# 02-MCU.net
KiCad netlist of a schematic drawn in Altium Designer
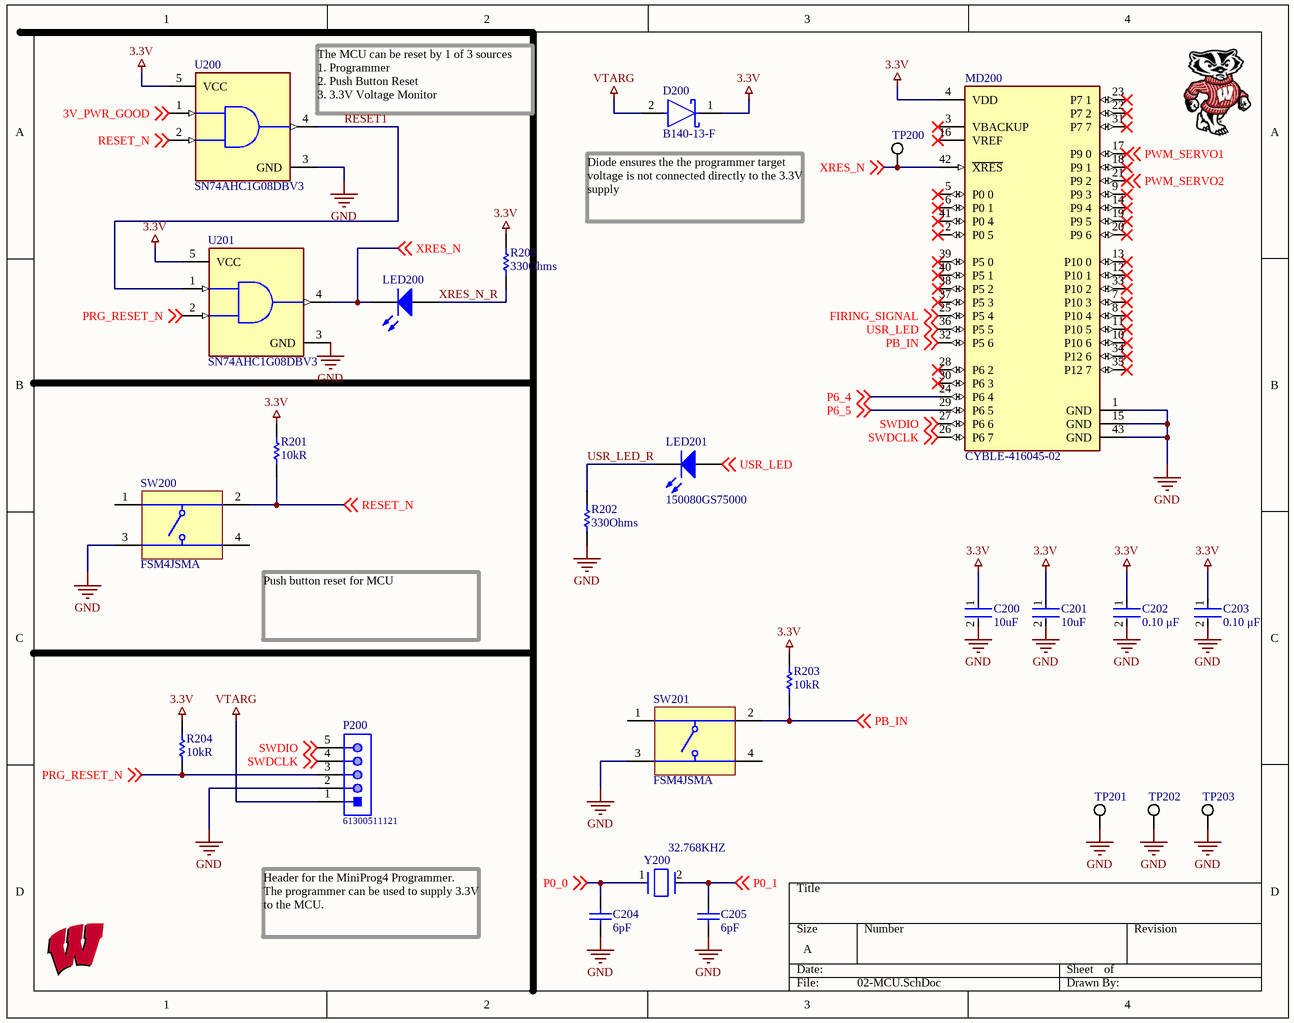
[diagram p0: 02-MCU.SchDoc]

(export (version "E")
  (design (tool "Eeschema 10.0.6"))
  (components
    (comp (ref "C200")
      (value "10uF")
      (footprint "FP-C0805C-DG-MFG")
      (description "CAP CER 10UF 10V X5R 0805")
      (fields (field (name "TOLERANCE") "10%") (field (name "MANUFACTURER PART NUMBER") "C0805C106K8PACTU"))
      (libsource (lib "Altium Content Vault") (part "11868f565c42a9108669ba33697ecf6"))
    )
    (comp (ref "C201")
      (value "10uF")
      (footprint "FP-C0805C-DG-MFG")
      (description "CAP CER 10UF 10V X5R 0805")
      (fields (field (name "TOLERANCE") "10%") (field (name "MANUFACTURER PART NUMBER") "C0805C106K8PACTU"))
      (libsource (lib "Altium Content Vault") (part "11868f565c42a9108669ba33697ecf6"))
    )
    (comp (ref "C202")
      (value "0.10 μF")
      (footprint "FP-C0805C-DN-MFG")
      (description "CAP CER 0.1UF 50V X7R 0805")
      (fields
        (field (name "MANUFACTURER PART NUMBER") "C0805C104K5RACTU")
        (field (name "MANUFACTURER") "KEMET")
      )
      (libsource (lib "Altium Content Vault") (part "b4654b650e69147ec39a6b967a45e02"))
    )
    (comp (ref "C203")
      (value "0.10 μF")
      (footprint "FP-C0805C-DN-MFG")
      (description "CAP CER 0.1UF 50V X7R 0805")
      (fields
        (field (name "MANUFACTURER PART NUMBER") "C0805C104K5RACTU")
        (field (name "MANUFACTURER") "KEMET")
      )
      (libsource (lib "Altium Content Vault") (part "b4654b650e69147ec39a6b967a45e02"))
    )
    (comp (ref "C204")
      (value "08055A6R0CAT2A")
      (footprint "CAPC2013X94X50LL20T25")
      (fields (field (name "MANUFACTURER") "AVX Interconnect / Elco") (field (name "CAPACITANCE") "6pF"))
      (libsource (lib "Altium Content Vault") (part "CAP"))
    )
    (comp (ref "C205")
      (value "08055A6R0CAT2A")
      (footprint "CAPC2013X94X50LL20T25")
      (fields (field (name "MANUFACTURER") "AVX Interconnect / Elco") (field (name "CAPACITANCE") "6pF"))
      (libsource (lib "Altium Content Vault") (part "CAP"))
    )
    (comp (ref "D200")
      (value "B140-13-F")
      (footprint "FP-SMA-MFG")
      (description "DIODE SCHOTTKY 40V 1A SMA")
      (libsource (lib "Altium Content Vault") (part "1d6ec82d83fb6aee721767c19dac4b9"))
    )
    (comp (ref "LED200")
      (value "150080RS75000")
      (footprint "0805_A")
      (description "SMD mono-color Chip LED, WL-SMCW, Red")
      (fields (field (name "MANUFACTURER") "Wuerth Elektronik"))
      (libsource (lib "Altium Content Vault") (part "WE-LED_K1A2-2"))
    )
    (comp (ref "LED201")
      (value "150080GS75000")
      (footprint "0805_A")
      (description "SMD mono-color Chip LED, WL-SMCW, Green")
      (fields (field (name "MANUFACTURER") "Wuerth Elektronik"))
      (libsource (lib "Altium Content Vault") (part "WE-LED_K1A2-2"))
    )
    (comp (ref "MD200")
      (value "CYBLE-416045-02")
      (footprint "FP-CYBLE-416045-02-MFG")
      (description "RF TXRX MOD BLUETOOTH TRACE ANT")
      (fields
        (field (name "OCTOPART") "https://octopart.com/cyble-416045-02-cypress+semiconductor-96386825")
        (field (name "MANUFACTURER") "Cypress Semiconductor")
      )
      (libsource (lib "Altium Content Vault") (part "10a29a4e77099fbb6f911efb04878b1"))
    )
    (comp (ref "P200")
      (value "61300511121")
      (footprint "61300511121")
      (description "THT Vertical Pin Header WR-PHD, Pitch 2.54 mm, Single Row, 5 pins")
      (fields (field (name "MANUFACTURER") "Wurth Elektronik") (field (name "PUBLISHER") "WurthElektronik"))
      (libsource (lib "Altium Content Vault") (part "WE-CN-1P-M-R5"))
    )
    (comp (ref "R200")
      (value "RC0805FR-07330RL")
      (footprint "RESC2013X60X35LL10T20")
      (description "Chip Resistor, 330 Ohm, +/- 1%, 125 mW, -55 to 155 degC, 0805 (2012 Metric), RoHS, Tape and Reel")
      (fields
        (field (name "MANUFACTURER") "Yageo")
        (field (name "TOLERANCE") "1%")
        (field (name "RESISTANCE") "330Ohms")
      )
      (libsource (lib "Altium Content Vault") (part "RES-2"))
    )
    (comp (ref "R201")
      (value "RC0805FR-0710KL")
      (footprint "RESC2013X60X35NL10T20")
      (description "Chip Resistor, 10 KOhm, +/- 1%, 0.125 W, -55 to 155 degC, 0805 (2012 Metric), RoHS, Tape and Reel")
      (fields
        (field (name "MANUFACTURER") "Yageo")
        (field (name "RESISTANCE") "10kR")
        (field (name "TOLERANCE") "1%")
      )
      (libsource (lib "Altium Content Vault") (part "RES-2"))
    )
    (comp (ref "R202")
      (value "RC0805FR-07330RL")
      (footprint "RESC2013X60X35LL10T20")
      (description "Chip Resistor, 330 Ohm, +/- 1%, 125 mW, -55 to 155 degC, 0805 (2012 Metric), RoHS, Tape and Reel")
      (fields
        (field (name "MANUFACTURER") "Yageo")
        (field (name "TOLERANCE") "1%")
        (field (name "RESISTANCE") "330Ohms")
      )
      (libsource (lib "Altium Content Vault") (part "RES-2"))
    )
    (comp (ref "R203")
      (value "RC0805FR-0710KL")
      (footprint "RESC2013X60X35NL10T20")
      (description "Chip Resistor, 10 KOhm, +/- 1%, 0.125 W, -55 to 155 degC, 0805 (2012 Metric), RoHS, Tape and Reel")
      (fields
        (field (name "MANUFACTURER") "Yageo")
        (field (name "RESISTANCE") "10kR")
        (field (name "TOLERANCE") "1%")
      )
      (libsource (lib "Altium Content Vault") (part "RES-2"))
    )
    (comp (ref "R204")
      (value "RC0805FR-0710KL")
      (footprint "RESC2013X60X35NL10T20")
      (description "Chip Resistor, 10 KOhm, +/- 1%, 0.125 W, -55 to 155 degC, 0805 (2012 Metric), RoHS, Tape and Reel")
      (fields
        (field (name "MANUFACTURER") "Yageo")
        (field (name "RESISTANCE") "10kR")
        (field (name "TOLERANCE") "1%")
      )
      (libsource (lib "Altium Content Vault") (part "RES-2"))
    )
    (comp (ref "SW200")
      (value "FSM4JSMA")
      (footprint "TECO-FSM4JSMA_V")
      (description "Swicth, SPST, 24 V, -35 to 85 degC, 4-Pin SMD, RoHS, Tape and Reel")
      (fields (field (name "MANUFACTURER") "TE Connectivity"))
      (libsource (lib "Altium Content Vault") (part "SW-SPST-4_A"))
    )
    (comp (ref "SW201")
      (value "FSM4JSMA")
      (footprint "TECO-FSM4JSMA_V")
      (description "Swicth, SPST, 24 V, -35 to 85 degC, 4-Pin SMD, RoHS, Tape and Reel")
      (fields (field (name "MANUFACTURER") "TE Connectivity"))
      (libsource (lib "Altium Content Vault") (part "SW-SPST-4_A"))
    )
    (comp (ref "TP200")
      (value "5019")
      (footprint "KSTN-5019_V")
      (description "Test Point, 1 Position SMD, RoHS, Tape and Reel")
      (libsource (lib "Altium Content Vault") (part "TESTPOINT_WHITE"))
    )
    (comp (ref "TP201")
      (value "5019")
      (footprint "KSTN-5019_V")
      (description "Test Point, 1 Position SMD, RoHS, Tape and Reel")
      (libsource (lib "Altium Content Vault") (part "TESTPOINT_WHITE"))
    )
    (comp (ref "TP202")
      (value "5019")
      (footprint "KSTN-5019_V")
      (description "Test Point, 1 Position SMD, RoHS, Tape and Reel")
      (libsource (lib "Altium Content Vault") (part "TESTPOINT_WHITE"))
    )
    (comp (ref "TP203")
      (value "5019")
      (footprint "KSTN-5019_V")
      (description "Test Point, 1 Position SMD, RoHS, Tape and Reel")
      (libsource (lib "Altium Content Vault") (part "TESTPOINT_WHITE"))
    )
    (comp (ref "U200")
      (value "SN74AHC1G08DBV3")
      (footprint "FP-DBV0005A-IPC_C")
      (description "IC GATE AND 1CH 2-INP SOT23-5")
      (libsource (lib "Altium Content Vault") (part "675e79b427d6219a5295bf943425e1c"))
    )
    (comp (ref "U201")
      (value "SN74AHC1G08DBV3")
      (footprint "FP-DBV0005A-IPC_C")
      (description "IC GATE AND 1CH 2-INP SOT23-5")
      (libsource (lib "Altium Content Vault") (part "675e79b427d6219a5295bf943425e1c"))
    )
    (comp (ref "Y200")
      (value "32.768KHZ")
      (footprint "FP-ABS07-120-MFG")
      (description "CRYSTAL 32.7680KHZ 6PF SMD")
      (fields (field (name "TOLERANCE") "20ppm"))
      (libsource (lib "Altium Content Vault") (part "c23a69dc6c9e2f18f2079038eb95dd1"))
    )
  )
  (nets
    (net (code "1") (name "/RESET1") (class "Default")
      (node (ref "U200") (pin "4") (pinfunction "Y_4") (pintype "output"))
      (node (ref "U201") (pin "1") (pinfunction "A_1") (pintype "input"))
    )
    (net (code "2") (name "/USR_LED_R") (class "Default")
      (node (ref "LED201") (pin "1") (pinfunction "K_1") (pintype "passive"))
      (node (ref "R202") (pin "2") (pinfunction "2_2") (pintype "passive"))
    )
    (net (code "3") (name "/XRES_N_R") (class "Default")
      (node (ref "LED200") (pin "2") (pinfunction "A_2") (pintype "passive"))
      (node (ref "R200") (pin "1") (pinfunction "1_1") (pintype "passive"))
    )
    (net (code "4") (name "3.3V") (class "Default")
      (node (ref "C200") (pin "1") (pinfunction "1_1") (pintype "passive"))
      (node (ref "C201") (pin "1") (pinfunction "1_1") (pintype "passive"))
      (node (ref "C202") (pin "1") (pinfunction "1_1") (pintype "passive"))
      (node (ref "C203") (pin "1") (pinfunction "1_1") (pintype "passive"))
      (node (ref "D200") (pin "1") (pinfunction "C_1") (pintype "passive"))
      (node (ref "MD200") (pin "4") (pinfunction "VDD_4") (pintype "power_in"))
      (node (ref "R200") (pin "2") (pinfunction "2_2") (pintype "passive"))
      (node (ref "R201") (pin "2") (pinfunction "2_2") (pintype "passive"))
      (node (ref "R203") (pin "2") (pinfunction "2_2") (pintype "passive"))
      (node (ref "R204") (pin "2") (pinfunction "2_2") (pintype "passive"))
      (node (ref "U200") (pin "5") (pinfunction "VCC_5") (pintype "power_in"))
      (node (ref "U201") (pin "5") (pinfunction "VCC_5") (pintype "power_in"))
    )
    (net (code "5") (name "3V_PWR_GOOD") (class "Default")
      (node (ref "U200") (pin "1") (pinfunction "A_1") (pintype "input"))
    )
    (net (code "6") (name "FIRING_SIGNAL") (class "Default")
      (node (ref "MD200") (pin "25") (pinfunction "P5_4_25") (pintype "bidirectional"))
    )
    (net (code "7") (name "GND") (class "Default")
      (node (ref "C200") (pin "2") (pinfunction "2_2") (pintype "passive"))
      (node (ref "C201") (pin "2") (pinfunction "2_2") (pintype "passive"))
      (node (ref "C202") (pin "2") (pinfunction "2_2") (pintype "passive"))
      (node (ref "C203") (pin "2") (pinfunction "2_2") (pintype "passive"))
      (node (ref "C204") (pin "1") (pinfunction "1_1") (pintype "passive"))
      (node (ref "C205") (pin "1") (pinfunction "1_1") (pintype "passive"))
      (node (ref "MD200") (pin "1") (pinfunction "GND_1") (pintype "power_in"))
      (node (ref "MD200") (pin "15") (pinfunction "GND_15") (pintype "power_in"))
      (node (ref "MD200") (pin "43") (pinfunction "GND_43") (pintype "power_in"))
      (node (ref "P200") (pin "2") (pinfunction "2_2") (pintype "passive"))
      (node (ref "R202") (pin "1") (pinfunction "1_1") (pintype "passive"))
      (node (ref "SW200") (pin "3") (pinfunction "3_3") (pintype "passive"))
      (node (ref "SW201") (pin "3") (pinfunction "3_3") (pintype "passive"))
      (node (ref "TP201") (pin "1") (pinfunction "1_1") (pintype "passive"))
      (node (ref "TP202") (pin "1") (pinfunction "1_1") (pintype "passive"))
      (node (ref "TP203") (pin "1") (pinfunction "1_1") (pintype "passive"))
      (node (ref "U200") (pin "3") (pinfunction "GND_3") (pintype "power_in"))
      (node (ref "U201") (pin "3") (pinfunction "GND_3") (pintype "power_in"))
    )
    (net (code "8") (name "P0_0") (class "Default")
      (node (ref "C204") (pin "2") (pinfunction "2_2") (pintype "passive"))
      (node (ref "Y200") (pin "1") (pinfunction "1_1") (pintype "passive"))
    )
    (net (code "9") (name "P0_1") (class "Default")
      (node (ref "C205") (pin "2") (pinfunction "2_2") (pintype "passive"))
      (node (ref "Y200") (pin "2") (pinfunction "2_2") (pintype "passive"))
    )
    (net (code "10") (name "P6_4") (class "Default")
      (node (ref "MD200") (pin "24") (pinfunction "P6_4_24") (pintype "bidirectional"))
    )
    (net (code "11") (name "P6_5") (class "Default")
      (node (ref "MD200") (pin "29") (pinfunction "P6_5_29") (pintype "bidirectional"))
    )
    (net (code "12") (name "PB_IN") (class "Default")
      (node (ref "MD200") (pin "32") (pinfunction "P5_6_32") (pintype "bidirectional"))
      (node (ref "R203") (pin "1") (pinfunction "1_1") (pintype "passive"))
      (node (ref "SW201") (pin "2") (pinfunction "2_2") (pintype "passive"))
    )
    (net (code "13") (name "PRG_RESET_N") (class "Default")
      (node (ref "P200") (pin "3") (pinfunction "3_3") (pintype "passive"))
      (node (ref "R204") (pin "1") (pinfunction "1_1") (pintype "passive"))
      (node (ref "U201") (pin "2") (pinfunction "B_2") (pintype "input"))
    )
    (net (code "14") (name "PWM_SERVO1") (class "Default")
      (node (ref "MD200") (pin "17") (pinfunction "P9_0_17") (pintype "bidirectional"))
    )
    (net (code "15") (name "PWM_SERVO2") (class "Default")
      (node (ref "MD200") (pin "21") (pinfunction "P9_2_21") (pintype "bidirectional"))
    )
    (net (code "16") (name "RESET_N") (class "Default")
      (node (ref "R201") (pin "1") (pinfunction "1_1") (pintype "passive"))
      (node (ref "SW200") (pin "2") (pinfunction "2_2") (pintype "passive"))
      (node (ref "U200") (pin "2") (pinfunction "B_2") (pintype "input"))
    )
    (net (code "17") (name "SWDCLK") (class "Default")
      (node (ref "MD200") (pin "26") (pinfunction "P6_7_26") (pintype "bidirectional"))
      (node (ref "P200") (pin "4") (pinfunction "4_4") (pintype "passive"))
    )
    (net (code "18") (name "SWDIO") (class "Default")
      (node (ref "MD200") (pin "27") (pinfunction "P6_6_27") (pintype "bidirectional"))
      (node (ref "P200") (pin "5") (pinfunction "5_5") (pintype "passive"))
    )
    (net (code "19") (name "USR_LED") (class "Default")
      (node (ref "LED201") (pin "2") (pinfunction "A_2") (pintype "passive"))
      (node (ref "MD200") (pin "36") (pinfunction "P5_5_36") (pintype "bidirectional"))
    )
    (net (code "20") (name "VTARG") (class "Default")
      (node (ref "D200") (pin "2") (pinfunction "A_2") (pintype "passive"))
      (node (ref "P200") (pin "1") (pinfunction "1_1") (pintype "passive"))
    )
    (net (code "21") (name "XRES_N") (class "Default")
      (node (ref "LED200") (pin "1") (pinfunction "K_1") (pintype "passive"))
      (node (ref "MD200") (pin "42") (pinfunction "~{XRES}_42") (pintype "input"))
      (node (ref "TP200") (pin "1") (pinfunction "1_1") (pintype "passive"))
      (node (ref "U201") (pin "4") (pinfunction "Y_4") (pintype "output"))
    )
    (net (code "22") (name "unconnected-(MD200-P0_0-Pad5)") (class "Default")
      (node (ref "MD200") (pin "5") (pinfunction "P0_0_5") (pintype "bidirectional+no_connect"))
    )
    (net (code "23") (name "unconnected-(MD200-P0_1-Pad6)") (class "Default")
      (node (ref "MD200") (pin "6") (pinfunction "P0_1_6") (pintype "bidirectional+no_connect"))
    )
    (net (code "24") (name "unconnected-(MD200-P0_4-Pad41)") (class "Default")
      (node (ref "MD200") (pin "41") (pinfunction "P0_4_41") (pintype "bidirectional+no_connect"))
    )
    (net (code "25") (name "unconnected-(MD200-P0_5-Pad2)") (class "Default")
      (node (ref "MD200") (pin "2") (pinfunction "P0_5_2") (pintype "bidirectional+no_connect"))
    )
    (net (code "26") (name "unconnected-(MD200-P5_0-Pad39)") (class "Default")
      (node (ref "MD200") (pin "39") (pinfunction "P5_0_39") (pintype "bidirectional+no_connect"))
    )
    (net (code "27") (name "unconnected-(MD200-P5_1-Pad40)") (class "Default")
      (node (ref "MD200") (pin "40") (pinfunction "P5_1_40") (pintype "bidirectional+no_connect"))
    )
    (net (code "28") (name "unconnected-(MD200-P5_2-Pad38)") (class "Default")
      (node (ref "MD200") (pin "38") (pinfunction "P5_2_38") (pintype "bidirectional+no_connect"))
    )
    (net (code "29") (name "unconnected-(MD200-P5_3-Pad37)") (class "Default")
      (node (ref "MD200") (pin "37") (pinfunction "P5_3_37") (pintype "bidirectional+no_connect"))
    )
    (net (code "30") (name "unconnected-(MD200-P6_2-Pad28)") (class "Default")
      (node (ref "MD200") (pin "28") (pinfunction "P6_2_28") (pintype "bidirectional+no_connect"))
    )
    (net (code "31") (name "unconnected-(MD200-P6_3-Pad30)") (class "Default")
      (node (ref "MD200") (pin "30") (pinfunction "P6_3_30") (pintype "bidirectional+no_connect"))
    )
    (net (code "32") (name "unconnected-(MD200-P7_1-Pad23)") (class "Default")
      (node (ref "MD200") (pin "23") (pinfunction "P7_1_23") (pintype "bidirectional+no_connect"))
    )
    (net (code "33") (name "unconnected-(MD200-P7_2-Pad22)") (class "Default")
      (node (ref "MD200") (pin "22") (pinfunction "P7_2_22") (pintype "bidirectional+no_connect"))
    )
    (net (code "34") (name "unconnected-(MD200-P7_7-Pad31)") (class "Default")
      (node (ref "MD200") (pin "31") (pinfunction "P7_7_31") (pintype "bidirectional+no_connect"))
    )
    (net (code "35") (name "unconnected-(MD200-P9_1-Pad18)") (class "Default")
      (node (ref "MD200") (pin "18") (pinfunction "P9_1_18") (pintype "bidirectional+no_connect"))
    )
    (net (code "36") (name "unconnected-(MD200-P9_3-Pad9)") (class "Default")
      (node (ref "MD200") (pin "9") (pinfunction "P9_3_9") (pintype "bidirectional+no_connect"))
    )
    (net (code "37") (name "unconnected-(MD200-P9_4-Pad14)") (class "Default")
      (node (ref "MD200") (pin "14") (pinfunction "P9_4_14") (pintype "bidirectional+no_connect"))
    )
    (net (code "38") (name "unconnected-(MD200-P9_5-Pad19)") (class "Default")
      (node (ref "MD200") (pin "19") (pinfunction "P9_5_19") (pintype "bidirectional+no_connect"))
    )
    (net (code "39") (name "unconnected-(MD200-P9_6-Pad20)") (class "Default")
      (node (ref "MD200") (pin "20") (pinfunction "P9_6_20") (pintype "bidirectional+no_connect"))
    )
    (net (code "40") (name "unconnected-(MD200-P10_0-Pad13)") (class "Default")
      (node (ref "MD200") (pin "13") (pinfunction "P10_0_13") (pintype "bidirectional+no_connect"))
    )
    (net (code "41") (name "unconnected-(MD200-P10_1-Pad12)") (class "Default")
      (node (ref "MD200") (pin "12") (pinfunction "P10_1_12") (pintype "bidirectional+no_connect"))
    )
    (net (code "42") (name "unconnected-(MD200-P10_2-Pad33)") (class "Default")
      (node (ref "MD200") (pin "33") (pinfunction "P10_2_33") (pintype "bidirectional+no_connect"))
    )
    (net (code "43") (name "unconnected-(MD200-P10_3-Pad7)") (class "Default")
      (node (ref "MD200") (pin "7") (pinfunction "P10_3_7") (pintype "bidirectional+no_connect"))
    )
    (net (code "44") (name "unconnected-(MD200-P10_4-Pad8)") (class "Default")
      (node (ref "MD200") (pin "8") (pinfunction "P10_4_8") (pintype "bidirectional+no_connect"))
    )
    (net (code "45") (name "unconnected-(MD200-P10_5-Pad11)") (class "Default")
      (node (ref "MD200") (pin "11") (pinfunction "P10_5_11") (pintype "bidirectional+no_connect"))
    )
    (net (code "46") (name "unconnected-(MD200-P10_6-Pad10)") (class "Default")
      (node (ref "MD200") (pin "10") (pinfunction "P10_6_10") (pintype "bidirectional+no_connect"))
    )
    (net (code "47") (name "unconnected-(MD200-P12_6-Pad34)") (class "Default")
      (node (ref "MD200") (pin "34") (pinfunction "P12_6_34") (pintype "bidirectional+no_connect"))
    )
    (net (code "48") (name "unconnected-(MD200-P12_7-Pad35)") (class "Default")
      (node (ref "MD200") (pin "35") (pinfunction "P12_7_35") (pintype "bidirectional+no_connect"))
    )
    (net (code "49") (name "unconnected-(MD200-VBACKUP-Pad3)") (class "Default")
      (node (ref "MD200") (pin "3") (pinfunction "VBACKUP_3") (pintype "power_in+no_connect"))
    )
    (net (code "50") (name "unconnected-(MD200-VREF-Pad16)") (class "Default")
      (node (ref "MD200") (pin "16") (pinfunction "VREF_16") (pintype "power_in+no_connect"))
    )
    (net (code "51") (name "unconnected-(SW200-Pad1)") (class "Default")
      (node (ref "SW200") (pin "1") (pinfunction "1_1") (pintype "passive"))
    )
    (net (code "52") (name "unconnected-(SW200-Pad4)") (class "Default")
      (node (ref "SW200") (pin "4") (pinfunction "4_4") (pintype "passive"))
    )
    (net (code "53") (name "unconnected-(SW201-Pad1)") (class "Default")
      (node (ref "SW201") (pin "1") (pinfunction "1_1") (pintype "passive"))
    )
    (net (code "54") (name "unconnected-(SW201-Pad4)") (class "Default")
      (node (ref "SW201") (pin "4") (pinfunction "4_4") (pintype "passive"))
    )
  )
)
